# StarControl.net
KiCad netlist of a schematic drawn in EAGLE
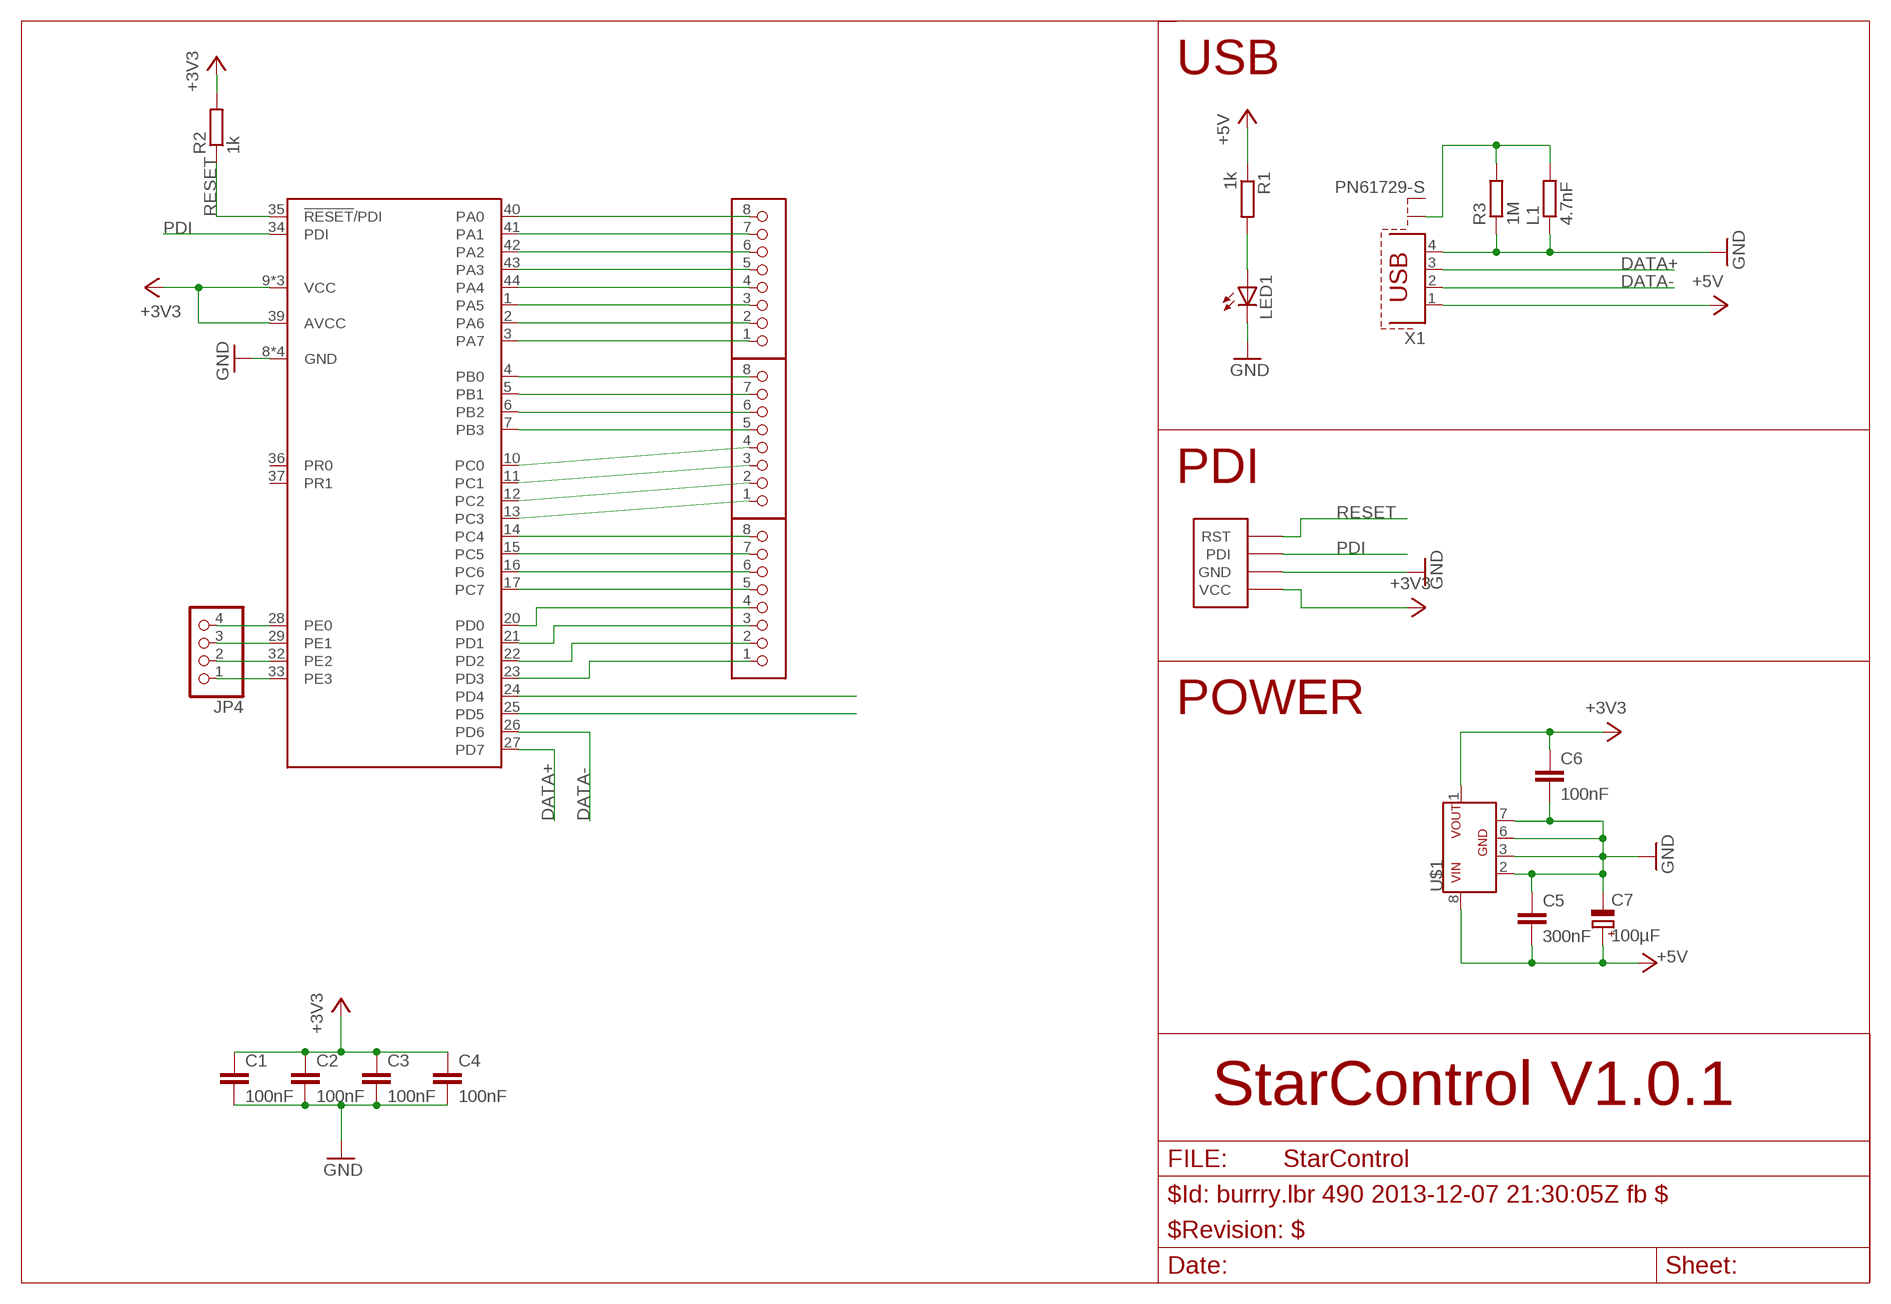
[diagram p0: schematic, sheet 1]

(export (version "E")
  (design (tool "Eeschema 10.0.6"))
  (components
    (comp (ref "C1")
      (value "100nF")
      (footprint "eagle-import:C0603K")
      (libsource (lib "eagle-import") (part "C-EUC0603K"))
    )
    (comp (ref "C2")
      (value "100nF")
      (footprint "eagle-import:C0603K")
      (libsource (lib "eagle-import") (part "C-EUC0603K"))
    )
    (comp (ref "C3")
      (value "100nF")
      (footprint "eagle-import:C0603K")
      (libsource (lib "eagle-import") (part "C-EUC0603K"))
    )
    (comp (ref "C4")
      (value "100nF")
      (footprint "eagle-import:C0603K")
      (libsource (lib "eagle-import") (part "C-EUC0603K"))
    )
    (comp (ref "C5")
      (value "300nF")
      (footprint "eagle-import:C1206")
      (libsource (lib "eagle-import") (part "C-EUC1206"))
    )
    (comp (ref "C6")
      (value "100nF")
      (footprint "eagle-import:C1206")
      (libsource (lib "eagle-import") (part "C-EUC1206"))
    )
    (comp (ref "C7")
      (value "100µF")
      (footprint "eagle-import:E2,5-5")
      (libsource (lib "eagle-import") (part "CPOL-EUE2.5-5"))
    )
    (comp (ref "JP4")
      (value "PINHD-1X4")
      (footprint "eagle-import:1X04")
      (libsource (lib "eagle-import") (part "PINHD-1X4"))
    )
    (comp (ref "L1")
      (value "4.7nF")
      (footprint "eagle-import:R0805")
      (libsource (lib "eagle-import") (part "R-EU_R0805"))
    )
    (comp (ref "LED1")
      (value "LED3MM")
      (footprint "eagle-import:LED3MM")
      (libsource (lib "eagle-import") (part "LED3MM"))
    )
    (comp (ref "R1")
      (value "1k")
      (footprint "eagle-import:R1206")
      (libsource (lib "eagle-import") (part "R-EU_R1206"))
    )
    (comp (ref "R2")
      (value "1k")
      (footprint "eagle-import:R0805")
      (libsource (lib "eagle-import") (part "R-EU_R0805"))
    )
    (comp (ref "R3")
      (value "1M")
      (footprint "eagle-import:R0805")
      (libsource (lib "eagle-import") (part "R-EU_R0805"))
    )
    (comp (ref "U$1")
      (value "L78L33ACD13T")
      (footprint "eagle-import:SO-08")
      (libsource (lib "eagle-import") (part "L78L33ACD13T"))
    )
    (comp (ref "U$2")
      (value "PDI-4PIN")
      (footprint "eagle-import:1X04")
      (libsource (lib "eagle-import") (part "PDI-4PIN"))
    )
    (comp (ref "U$3")
      (value "AKL059-08")
      (footprint "eagle-import:AKL059-08")
      (libsource (lib "eagle-import") (part "AKL059-08"))
    )
    (comp (ref "U$4")
      (value "AKL059-08")
      (footprint "eagle-import:AKL059-08")
      (libsource (lib "eagle-import") (part "AKL059-08"))
    )
    (comp (ref "U$5")
      (value "AKL059-08")
      (footprint "eagle-import:AKL059-08")
      (libsource (lib "eagle-import") (part "AKL059-08"))
    )
    (comp (ref "U1")
      (value "ATXMEGA16C4-AU")
      (footprint "eagle-import:TQFP-44A-44")
      (libsource (lib "eagle-import") (part "ATXMEGA16C4-AU"))
    )
    (comp (ref "X1")
      (value "PN61729-S")
      (footprint "eagle-import:PN61729-S")
      (libsource (lib "eagle-import") (part "PN61729-S"))
    )
  )
  (nets
    (net (code "1") (name "+3V3") (class "Default")
      (node (ref "C1") (pin "1") (pinfunction "1_1") (pintype "passive"))
      (node (ref "C2") (pin "1") (pinfunction "1_1") (pintype "passive"))
      (node (ref "C3") (pin "1") (pinfunction "1_1") (pintype "passive"))
      (node (ref "C4") (pin "1") (pinfunction "1_1") (pintype "passive"))
      (node (ref "C6") (pin "1") (pinfunction "1_1") (pintype "passive"))
      (node (ref "R2") (pin "2") (pinfunction "2_2") (pintype "passive"))
      (node (ref "U$1") (pin "1") (pinfunction "1_1") (pintype "bidirectional"))
      (node (ref "U$2") (pin "4") (pinfunction "VCC_4") (pintype "power_in"))
      (node (ref "U1") (pin "19") (pinfunction "VCC_19") (pintype "power_in"))
      (node (ref "U1") (pin "31") (pinfunction "VCC_31") (pintype "power_in"))
      (node (ref "U1") (pin "39") (pinfunction "AVCC_39") (pintype "power_in"))
      (node (ref "U1") (pin "9") (pinfunction "VCC_9") (pintype "power_in"))
    )
    (net (code "2") (name "+5V") (class "Default")
      (node (ref "C5") (pin "2") (pinfunction "2_2") (pintype "passive"))
      (node (ref "C7") (pin "+") (pinfunction "+_+") (pintype "passive"))
      (node (ref "R1") (pin "1") (pinfunction "1_1") (pintype "passive"))
      (node (ref "U$1") (pin "8") (pinfunction "8_8") (pintype "bidirectional"))
      (node (ref "X1") (pin "1") (pinfunction "1_1") (pintype "passive"))
    )
    (net (code "3") (name "/DATA+") (class "Default")
      (node (ref "U1") (pin "27") (pinfunction "PD7_27") (pintype "bidirectional"))
      (node (ref "X1") (pin "3") (pinfunction "3_3") (pintype "passive"))
    )
    (net (code "4") (name "/DATA-") (class "Default")
      (node (ref "U1") (pin "26") (pinfunction "PD6_26") (pintype "bidirectional"))
      (node (ref "X1") (pin "2") (pinfunction "2_2") (pintype "passive"))
    )
    (net (code "5") (name "/PDI") (class "Default")
      (node (ref "U$2") (pin "1") (pinfunction "PDI_1") (pintype "bidirectional"))
      (node (ref "U1") (pin "34") (pinfunction "PDI_34") (pintype "bidirectional"))
    )
    (net (code "6") (name "/RESET") (class "Default")
      (node (ref "R2") (pin "1") (pinfunction "1_1") (pintype "passive"))
      (node (ref "U$2") (pin "3") (pinfunction "RST_3") (pintype "bidirectional"))
      (node (ref "U1") (pin "35") (pinfunction "~{RESET}/PDI_35") (pintype "bidirectional"))
    )
    (net (code "7") (name "GND") (class "Default")
      (node (ref "C1") (pin "2") (pinfunction "2_2") (pintype "passive"))
      (node (ref "C2") (pin "2") (pinfunction "2_2") (pintype "passive"))
      (node (ref "C3") (pin "2") (pinfunction "2_2") (pintype "passive"))
      (node (ref "C4") (pin "2") (pinfunction "2_2") (pintype "passive"))
      (node (ref "C5") (pin "1") (pinfunction "1_1") (pintype "passive"))
      (node (ref "C6") (pin "2") (pinfunction "2_2") (pintype "passive"))
      (node (ref "C7") (pin "-") (pinfunction "-_-") (pintype "passive"))
      (node (ref "L1") (pin "1") (pinfunction "1_1") (pintype "passive"))
      (node (ref "LED1") (pin "K") (pinfunction "C_K") (pintype "passive"))
      (node (ref "R3") (pin "1") (pinfunction "1_1") (pintype "passive"))
      (node (ref "U$1") (pin "2") (pinfunction "2_2") (pintype "bidirectional"))
      (node (ref "U$1") (pin "3") (pinfunction "3_3") (pintype "bidirectional"))
      (node (ref "U$1") (pin "6") (pinfunction "6_6") (pintype "bidirectional"))
      (node (ref "U$1") (pin "7") (pinfunction "7_7") (pintype "bidirectional"))
      (node (ref "U$2") (pin "2") (pinfunction "GND_2") (pintype "power_in"))
      (node (ref "U1") (pin "18") (pinfunction "GND_18") (pintype "power_in"))
      (node (ref "U1") (pin "30") (pinfunction "GND_30") (pintype "power_in"))
      (node (ref "U1") (pin "38") (pinfunction "GND_38") (pintype "power_in"))
      (node (ref "U1") (pin "8") (pinfunction "GND_8") (pintype "power_in"))
      (node (ref "X1") (pin "4") (pinfunction "4_4") (pintype "passive"))
    )
    (net (code "8") (name "Net-(L1-Pad2)") (class "Default")
      (node (ref "L1") (pin "2") (pinfunction "2_2") (pintype "passive"))
      (node (ref "R3") (pin "2") (pinfunction "2_2") (pintype "passive"))
      (node (ref "X1") (pin "S1") (pinfunction "S1_S1") (pintype "passive"))
    )
    (net (code "9") (name "Net-(LED1-PadA)") (class "Default")
      (node (ref "LED1") (pin "A") (pinfunction "A_A") (pintype "passive"))
      (node (ref "R1") (pin "2") (pinfunction "2_2") (pintype "passive"))
    )
    (net (code "10") (name "Net-(U1-PA0)") (class "Default")
      (node (ref "U$4") (pin "8") (pinfunction "8_8") (pintype "bidirectional"))
      (node (ref "U1") (pin "40") (pinfunction "PA0_40") (pintype "bidirectional"))
    )
    (net (code "11") (name "Net-(U1-PA1)") (class "Default")
      (node (ref "U$4") (pin "7") (pinfunction "7_7") (pintype "bidirectional"))
      (node (ref "U1") (pin "41") (pinfunction "PA1_41") (pintype "bidirectional"))
    )
    (net (code "12") (name "Net-(U1-PA2)") (class "Default")
      (node (ref "U$4") (pin "6") (pinfunction "6_6") (pintype "bidirectional"))
      (node (ref "U1") (pin "42") (pinfunction "PA2_42") (pintype "bidirectional"))
    )
    (net (code "13") (name "Net-(U1-PA3)") (class "Default")
      (node (ref "U$4") (pin "5") (pinfunction "5_5") (pintype "bidirectional"))
      (node (ref "U1") (pin "43") (pinfunction "PA3_43") (pintype "bidirectional"))
    )
    (net (code "14") (name "Net-(U1-PA4)") (class "Default")
      (node (ref "U$4") (pin "4") (pinfunction "4_4") (pintype "bidirectional"))
      (node (ref "U1") (pin "44") (pinfunction "PA4_44") (pintype "bidirectional"))
    )
    (net (code "15") (name "Net-(U1-PA5)") (class "Default")
      (node (ref "U$4") (pin "3") (pinfunction "3_3") (pintype "bidirectional"))
      (node (ref "U1") (pin "1") (pinfunction "PA5_1") (pintype "bidirectional"))
    )
    (net (code "16") (name "Net-(U1-PA6)") (class "Default")
      (node (ref "U$4") (pin "2") (pinfunction "2_2") (pintype "bidirectional"))
      (node (ref "U1") (pin "2") (pinfunction "PA6_2") (pintype "bidirectional"))
    )
    (net (code "17") (name "Net-(U1-PA7)") (class "Default")
      (node (ref "U$4") (pin "1") (pinfunction "1_1") (pintype "bidirectional"))
      (node (ref "U1") (pin "3") (pinfunction "PA7_3") (pintype "bidirectional"))
    )
    (net (code "18") (name "Net-(U1-PB0)") (class "Default")
      (node (ref "U$5") (pin "8") (pinfunction "8_8") (pintype "bidirectional"))
      (node (ref "U1") (pin "4") (pinfunction "PB0_4") (pintype "bidirectional"))
    )
    (net (code "19") (name "Net-(U1-PB1)") (class "Default")
      (node (ref "U$5") (pin "7") (pinfunction "7_7") (pintype "bidirectional"))
      (node (ref "U1") (pin "5") (pinfunction "PB1_5") (pintype "bidirectional"))
    )
    (net (code "20") (name "Net-(U1-PB2)") (class "Default")
      (node (ref "U$5") (pin "6") (pinfunction "6_6") (pintype "bidirectional"))
      (node (ref "U1") (pin "6") (pinfunction "PB2_6") (pintype "bidirectional"))
    )
    (net (code "21") (name "Net-(U1-PB3)") (class "Default")
      (node (ref "U$5") (pin "5") (pinfunction "5_5") (pintype "bidirectional"))
      (node (ref "U1") (pin "7") (pinfunction "PB3_7") (pintype "bidirectional"))
    )
    (net (code "22") (name "Net-(U1-PC0)") (class "Default")
      (node (ref "U$5") (pin "4") (pinfunction "4_4") (pintype "bidirectional"))
      (node (ref "U1") (pin "10") (pinfunction "PC0_10") (pintype "bidirectional"))
    )
    (net (code "23") (name "Net-(U1-PC1)") (class "Default")
      (node (ref "U$5") (pin "3") (pinfunction "3_3") (pintype "bidirectional"))
      (node (ref "U1") (pin "11") (pinfunction "PC1_11") (pintype "bidirectional"))
    )
    (net (code "24") (name "Net-(U1-PC2)") (class "Default")
      (node (ref "U$5") (pin "2") (pinfunction "2_2") (pintype "bidirectional"))
      (node (ref "U1") (pin "12") (pinfunction "PC2_12") (pintype "bidirectional"))
    )
    (net (code "25") (name "Net-(U1-PC3)") (class "Default")
      (node (ref "U$5") (pin "1") (pinfunction "1_1") (pintype "bidirectional"))
      (node (ref "U1") (pin "13") (pinfunction "PC3_13") (pintype "bidirectional"))
    )
    (net (code "26") (name "Net-(U1-PC4)") (class "Default")
      (node (ref "U$3") (pin "8") (pinfunction "8_8") (pintype "bidirectional"))
      (node (ref "U1") (pin "14") (pinfunction "PC4_14") (pintype "bidirectional"))
    )
    (net (code "27") (name "Net-(U1-PC5)") (class "Default")
      (node (ref "U$3") (pin "7") (pinfunction "7_7") (pintype "bidirectional"))
      (node (ref "U1") (pin "15") (pinfunction "PC5_15") (pintype "bidirectional"))
    )
    (net (code "28") (name "Net-(U1-PC6)") (class "Default")
      (node (ref "U$3") (pin "6") (pinfunction "6_6") (pintype "bidirectional"))
      (node (ref "U1") (pin "16") (pinfunction "PC6_16") (pintype "bidirectional"))
    )
    (net (code "29") (name "Net-(U1-PC7)") (class "Default")
      (node (ref "U$3") (pin "5") (pinfunction "5_5") (pintype "bidirectional"))
      (node (ref "U1") (pin "17") (pinfunction "PC7_17") (pintype "bidirectional"))
    )
    (net (code "30") (name "Net-(U1-PD0)") (class "Default")
      (node (ref "U$3") (pin "4") (pinfunction "4_4") (pintype "bidirectional"))
      (node (ref "U1") (pin "20") (pinfunction "PD0_20") (pintype "bidirectional"))
    )
    (net (code "31") (name "Net-(U1-PD1)") (class "Default")
      (node (ref "U$3") (pin "3") (pinfunction "3_3") (pintype "bidirectional"))
      (node (ref "U1") (pin "21") (pinfunction "PD1_21") (pintype "bidirectional"))
    )
    (net (code "32") (name "Net-(U1-PD2)") (class "Default")
      (node (ref "U$3") (pin "2") (pinfunction "2_2") (pintype "bidirectional"))
      (node (ref "U1") (pin "22") (pinfunction "PD2_22") (pintype "bidirectional"))
    )
    (net (code "33") (name "Net-(U1-PD3)") (class "Default")
      (node (ref "U$3") (pin "1") (pinfunction "1_1") (pintype "bidirectional"))
      (node (ref "U1") (pin "23") (pinfunction "PD3_23") (pintype "bidirectional"))
    )
    (net (code "34") (name "Net-(U1-PE0)") (class "Default")
      (node (ref "JP4") (pin "4") (pinfunction "4_4") (pintype "passive"))
      (node (ref "U1") (pin "28") (pinfunction "PE0_28") (pintype "bidirectional"))
    )
    (net (code "35") (name "Net-(U1-PE1)") (class "Default")
      (node (ref "JP4") (pin "3") (pinfunction "3_3") (pintype "passive"))
      (node (ref "U1") (pin "29") (pinfunction "PE1_29") (pintype "bidirectional"))
    )
    (net (code "36") (name "Net-(U1-PE2)") (class "Default")
      (node (ref "JP4") (pin "2") (pinfunction "2_2") (pintype "passive"))
      (node (ref "U1") (pin "32") (pinfunction "PE2_32") (pintype "bidirectional"))
    )
    (net (code "37") (name "Net-(U1-PE3)") (class "Default")
      (node (ref "JP4") (pin "1") (pinfunction "1_1") (pintype "passive"))
      (node (ref "U1") (pin "33") (pinfunction "PE3_33") (pintype "bidirectional"))
    )
    (net (code "38") (name "unconnected-(U1-PD4-Pad24)") (class "Default")
      (node (ref "U1") (pin "24") (pinfunction "PD4_24") (pintype "bidirectional"))
    )
    (net (code "39") (name "unconnected-(U1-PD5-Pad25)") (class "Default")
      (node (ref "U1") (pin "25") (pinfunction "PD5_25") (pintype "bidirectional"))
    )
    (net (code "40") (name "unconnected-(U1-PR0-Pad36)") (class "Default")
      (node (ref "U1") (pin "36") (pinfunction "PR0_36") (pintype "bidirectional"))
    )
    (net (code "41") (name "unconnected-(U1-PR1-Pad37)") (class "Default")
      (node (ref "U1") (pin "37") (pinfunction "PR1_37") (pintype "bidirectional"))
    )
    (net (code "42") (name "unconnected-(X1-PadS2)") (class "Default")
      (node (ref "X1") (pin "S2") (pinfunction "S2_S2") (pintype "passive"))
    )
  )
)
